# 12V_to_3V3.net
KiCad netlist of a schematic drawn in Altium Designer
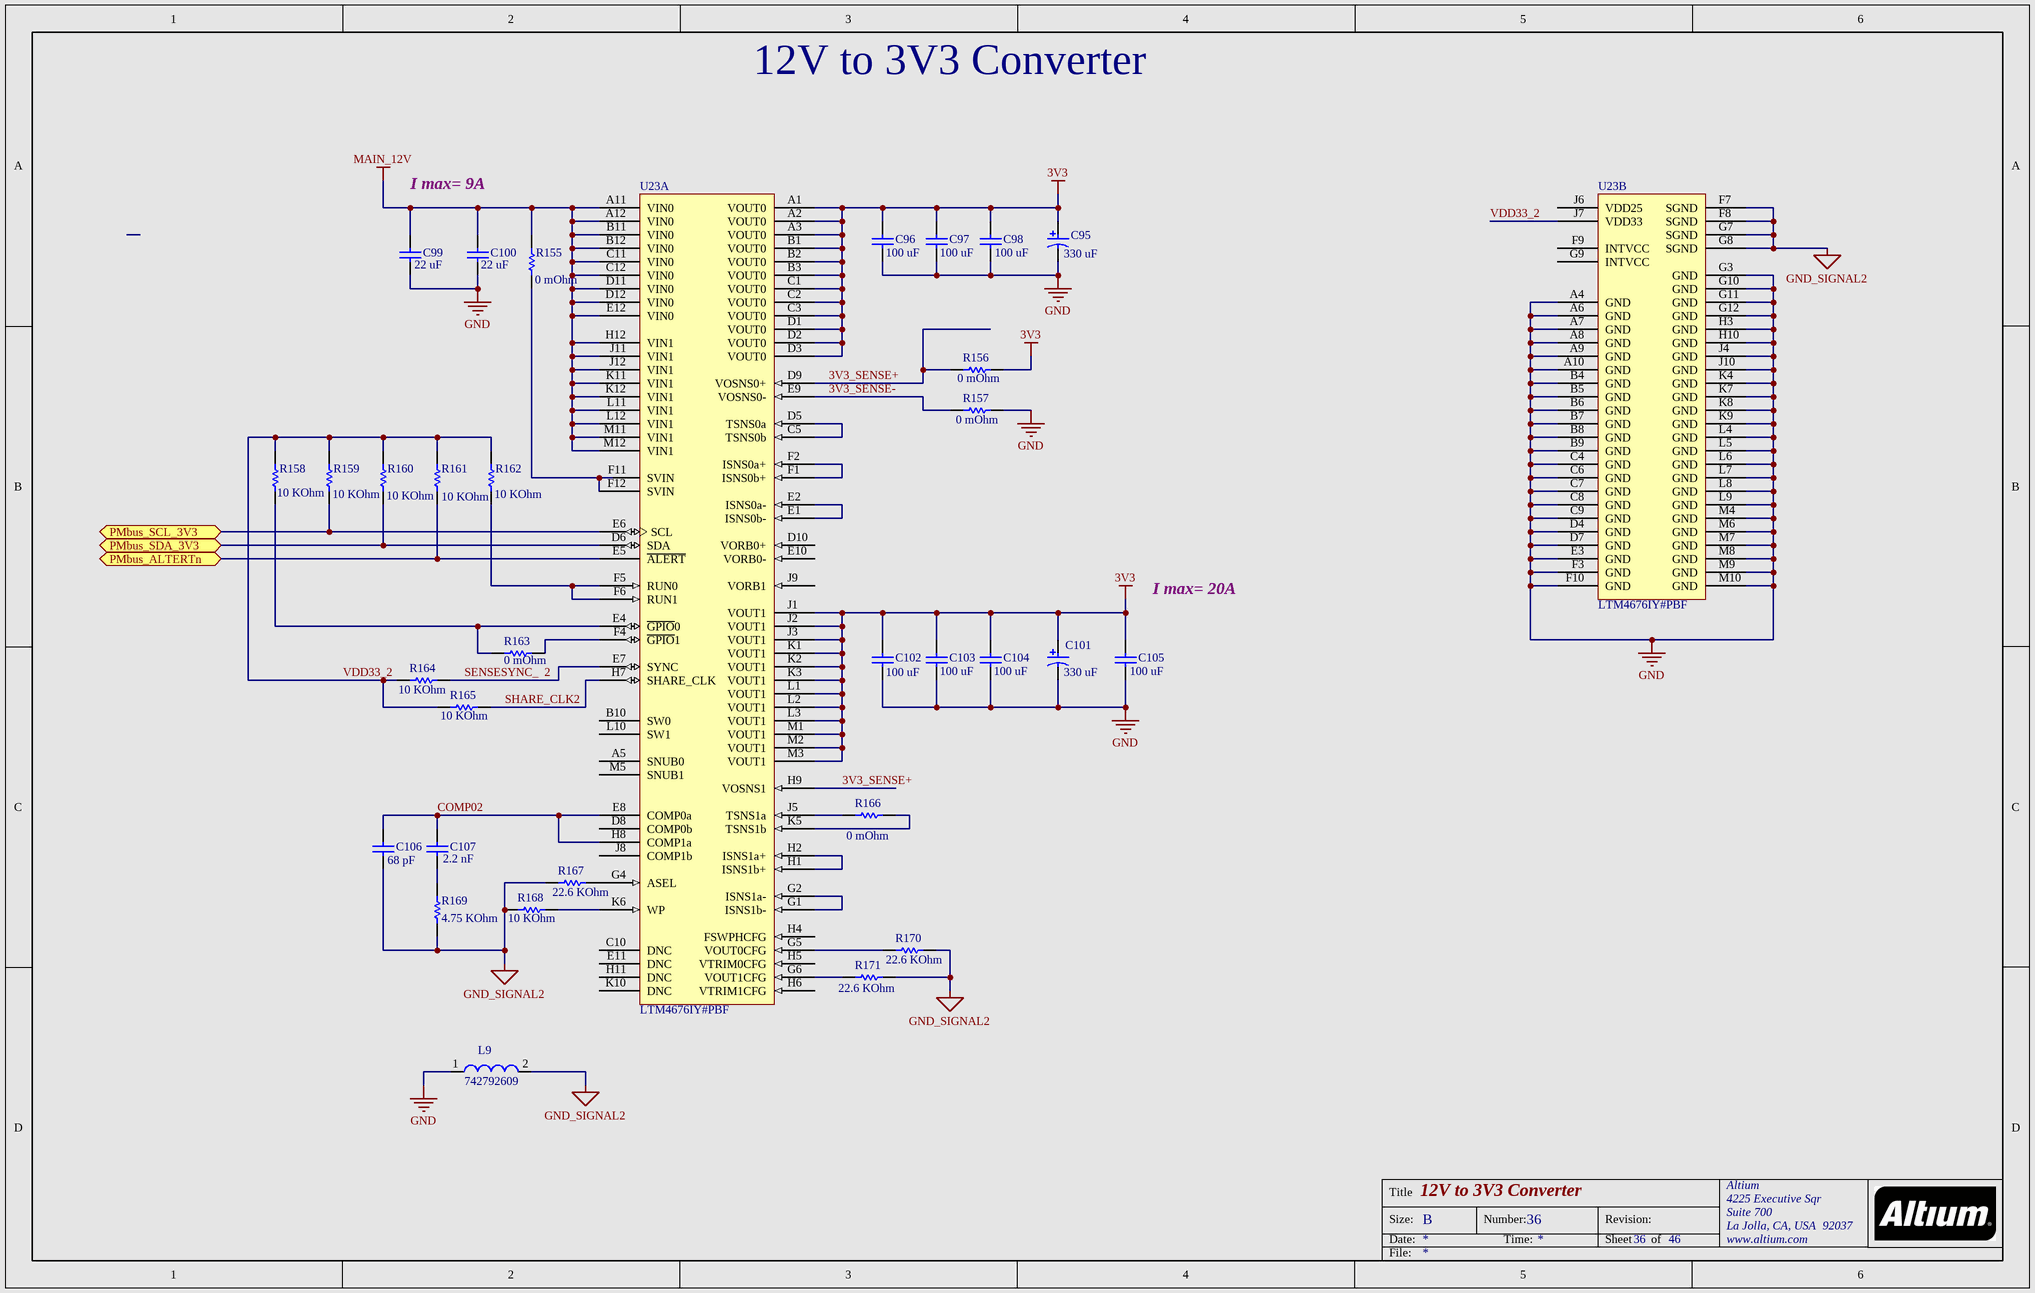
[diagram p0: 12V_to_3V3.SchDoc]

(export (version "E")
  (design (tool "Eeschema 10.0.6"))
  (components
    (comp (ref "C95")
      (value "6TPF330M9L")
      (footprint "PNSC-TPF-D3L_V")
      (description "Tantalum Capacitor, 330 uF, +/- 20%, 6.3 V, -55 to 105 degC, 2-Pin Molded, RoHS, Tape and Reel")
      (fields (field (name "CAPACITANCE") "330 uF"))
      (libsource (lib "Altium Content Vault") (part "CMP-1665-00019-2"))
    )
    (comp (ref "C96")
      (value "GRM31CR60J107ME39L")
      (footprint "CAPC3216X190X55ML30T25")
      (description "Chip Capacitor, 100 uF, +/- 20%, 6.3 V, -55 to 85 degC, 1206 (3216 Metric), RoHS, Tape and Reel")
      (fields (field (name "TOLERANCE") "20%") (field (name "CAPACITANCE") "100 uF"))
      (libsource (lib "Altium Content Vault") (part "CAP-NP-2"))
    )
    (comp (ref "C97")
      (value "GRM31CR60J107ME39L")
      (footprint "CAPC3216X190X55ML30T25")
      (description "Chip Capacitor, 100 uF, +/- 20%, 6.3 V, -55 to 85 degC, 1206 (3216 Metric), RoHS, Tape and Reel")
      (fields (field (name "TOLERANCE") "20%") (field (name "CAPACITANCE") "100 uF"))
      (libsource (lib "Altium Content Vault") (part "CAP-NP-2"))
    )
    (comp (ref "C98")
      (value "GRM31CR60J107ME39L")
      (footprint "CAPC3216X190X55ML30T25")
      (description "Chip Capacitor, 100 uF, +/- 20%, 6.3 V, -55 to 85 degC, 1206 (3216 Metric), RoHS, Tape and Reel")
      (fields (field (name "TOLERANCE") "20%") (field (name "CAPACITANCE") "100 uF"))
      (libsource (lib "Altium Content Vault") (part "CAP-NP-2"))
    )
    (comp (ref "C99")
      (value "GRM31CR61E226KE15L")
      (footprint "CAPC3216X180X55ML20T25")
      (description "Chip Capacitor, 22 uF, +/- 10%, 25 V, -55 to 85 degC, 1206 (3216 Metric), RoHS, Tape and Reel")
      (fields (field (name "TOLERANCE") "10%") (field (name "CAPACITANCE") "22 uF"))
      (libsource (lib "Altium Content Vault") (part "CAP-NP-2"))
    )
    (comp (ref "C100")
      (value "GRM31CR61E226KE15L")
      (footprint "CAPC3216X180X55ML20T25")
      (description "Chip Capacitor, 22 uF, +/- 10%, 25 V, -55 to 85 degC, 1206 (3216 Metric), RoHS, Tape and Reel")
      (fields (field (name "TOLERANCE") "10%") (field (name "CAPACITANCE") "22 uF"))
      (libsource (lib "Altium Content Vault") (part "CAP-NP-2"))
    )
    (comp (ref "C101")
      (value "6TPF330M9L")
      (footprint "PNSC-TPF-D3L_V")
      (description "Tantalum Capacitor, 330 uF, +/- 20%, 6.3 V, -55 to 105 degC, 2-Pin Molded, RoHS, Tape and Reel")
      (fields (field (name "CAPACITANCE") "330 uF"))
      (libsource (lib "Altium Content Vault") (part "CMP-1665-00019-2"))
    )
    (comp (ref "C102")
      (value "GRM31CR60J107ME39L")
      (footprint "CAPC3216X190X55ML30T25")
      (description "Chip Capacitor, 100 uF, +/- 20%, 6.3 V, -55 to 85 degC, 1206 (3216 Metric), RoHS, Tape and Reel")
      (fields (field (name "TOLERANCE") "20%") (field (name "CAPACITANCE") "100 uF"))
      (libsource (lib "Altium Content Vault") (part "CAP-NP-2"))
    )
    (comp (ref "C103")
      (value "GRM31CR60J107ME39L")
      (footprint "CAPC3216X190X55ML30T25")
      (description "Chip Capacitor, 100 uF, +/- 20%, 6.3 V, -55 to 85 degC, 1206 (3216 Metric), RoHS, Tape and Reel")
      (fields (field (name "TOLERANCE") "20%") (field (name "CAPACITANCE") "100 uF"))
      (libsource (lib "Altium Content Vault") (part "CAP-NP-2"))
    )
    (comp (ref "C104")
      (value "GRM31CR60J107ME39L")
      (footprint "CAPC3216X190X55ML30T25")
      (description "Chip Capacitor, 100 uF, +/- 20%, 6.3 V, -55 to 85 degC, 1206 (3216 Metric), RoHS, Tape and Reel")
      (fields (field (name "TOLERANCE") "20%") (field (name "CAPACITANCE") "100 uF"))
      (libsource (lib "Altium Content Vault") (part "CAP-NP-2"))
    )
    (comp (ref "C105")
      (value "GRM31CR60J107ME39L")
      (footprint "CAPC3216X190X55ML30T25")
      (description "Chip Capacitor, 100 uF, +/- 20%, 6.3 V, -55 to 85 degC, 1206 (3216 Metric), RoHS, Tape and Reel")
      (fields (field (name "TOLERANCE") "20%") (field (name "CAPACITANCE") "100 uF"))
      (libsource (lib "Altium Content Vault") (part "CAP-NP-2"))
    )
    (comp (ref "C106")
      (value "ECJ-0EC1H680J")
      (footprint "CAPC1005X55X20ML5T10")
      (description "Chip Capacitor, 68 pF, +/- 5%, 50 V, -55 to 125 degC, 0402 (1005 Metric), RoHS, Tape and Reel")
      (fields (field (name "TOLERANCE") "5%") (field (name "CAPACITANCE") "68 pF"))
      (libsource (lib "Altium Content Vault") (part "CMP-1665-00023-1"))
    )
    (comp (ref "C107")
      (value "CGJ2B2X7R1E222K050BA")
      (footprint "CAPC1005X55X10ML05")
      (description "Chip Capacitor, 2.2 nF, +/- 10%, 25 V, -55 to 125 degC, 0402 (1005 Metric), RoHS, Tape and Reel")
      (fields (field (name "TOLERANCE") "10%") (field (name "CAPACITANCE") "2.2 nF"))
      (libsource (lib "Altium Content Vault") (part "CAP-NP-2"))
    )
    (comp (ref "L9")
      (value "742792609")
      (footprint "SMD-0603")
      (description "SMD EMI Suppression Ferrite Bead WE-CBF, Z = 30 Ohm")
      (libsource (lib "Altium Content Vault") (part "CMP-0220-00193-1"))
    )
    (comp (ref "R155")
      (value "ERJ-2GE0R00X")
      (footprint "RESC1005X40X25ML05T05")
      (description "Chip Resistor, 0 mOhm, +/- 5%, 100 mW, -55 to 155 degC, 0402 (1005 Metric), RoHS, Tape and Reel")
      (fields
        (field (name "TOLERANCE") "5%")
        (field (name "RESISTANCE") "0 mOhm")
        (field (name "MANUFACTURER") "Basic Passives")
      )
      (libsource (lib "Altium Content Vault") (part "RES-2"))
    )
    (comp (ref "R156")
      (value "ERJ-2GE0R00X")
      (footprint "RESC1005X40X25ML05T05")
      (description "Chip Resistor, 0 mOhm, +/- 5%, 100 mW, -55 to 155 degC, 0402 (1005 Metric), RoHS, Tape and Reel")
      (fields
        (field (name "TOLERANCE") "5%")
        (field (name "RESISTANCE") "0 mOhm")
        (field (name "MANUFACTURER") "Basic Passives")
      )
      (libsource (lib "Altium Content Vault") (part "RES-2"))
    )
    (comp (ref "R157")
      (value "ERJ-2GE0R00X")
      (footprint "RESC1005X40X25ML05T05")
      (description "Chip Resistor, 0 mOhm, +/- 5%, 100 mW, -55 to 155 degC, 0402 (1005 Metric), RoHS, Tape and Reel")
      (fields
        (field (name "TOLERANCE") "5%")
        (field (name "RESISTANCE") "0 mOhm")
        (field (name "MANUFACTURER") "Basic Passives")
      )
      (libsource (lib "Altium Content Vault") (part "RES-2"))
    )
    (comp (ref "R158")
      (value "ERJ-2RKF1002X")
      (footprint "RESC1005X40X25NL05T05")
      (description "Chip Resistor, 10 KOhm, +/- 1%, 100 mW, -55 to 155 degC, 0402 (1005 Metric), RoHS, Tape and Reel")
      (fields
        (field (name "TOLERANCE") "1%")
        (field (name "RESISTANCE") "10 KOhm")
        (field (name "MANUFACTURER") "Basic Passives")
      )
      (libsource (lib "Altium Content Vault") (part "RES-2"))
    )
    (comp (ref "R159")
      (value "ERJ-2RKF1002X")
      (footprint "RESC1005X40X25NL05T05")
      (description "Chip Resistor, 10 KOhm, +/- 1%, 100 mW, -55 to 155 degC, 0402 (1005 Metric), RoHS, Tape and Reel")
      (fields
        (field (name "TOLERANCE") "1%")
        (field (name "RESISTANCE") "10 KOhm")
        (field (name "MANUFACTURER") "Basic Passives")
      )
      (libsource (lib "Altium Content Vault") (part "RES-2"))
    )
    (comp (ref "R160")
      (value "ERJ-2RKF1002X")
      (footprint "RESC1005X40X25NL05T05")
      (description "Chip Resistor, 10 KOhm, +/- 1%, 100 mW, -55 to 155 degC, 0402 (1005 Metric), RoHS, Tape and Reel")
      (fields
        (field (name "TOLERANCE") "1%")
        (field (name "RESISTANCE") "10 KOhm")
        (field (name "MANUFACTURER") "Basic Passives")
      )
      (libsource (lib "Altium Content Vault") (part "RES-2"))
    )
    (comp (ref "R161")
      (value "ERJ-2RKF1002X")
      (footprint "RESC1005X40X25NL05T05")
      (description "Chip Resistor, 10 KOhm, +/- 1%, 100 mW, -55 to 155 degC, 0402 (1005 Metric), RoHS, Tape and Reel")
      (fields
        (field (name "TOLERANCE") "1%")
        (field (name "RESISTANCE") "10 KOhm")
        (field (name "MANUFACTURER") "Basic Passives")
      )
      (libsource (lib "Altium Content Vault") (part "RES-2"))
    )
    (comp (ref "R162")
      (value "ERJ-2RKF1002X")
      (footprint "RESC1005X40X25NL05T05")
      (description "Chip Resistor, 10 KOhm, +/- 1%, 100 mW, -55 to 155 degC, 0402 (1005 Metric), RoHS, Tape and Reel")
      (fields
        (field (name "TOLERANCE") "1%")
        (field (name "RESISTANCE") "10 KOhm")
        (field (name "MANUFACTURER") "Basic Passives")
      )
      (libsource (lib "Altium Content Vault") (part "RES-2"))
    )
    (comp (ref "R163")
      (value "ERJ-2GE0R00X")
      (footprint "RESC1005X40X25ML05T05")
      (description "Chip Resistor, 0 mOhm, +/- 5%, 100 mW, -55 to 155 degC, 0402 (1005 Metric), RoHS, Tape and Reel")
      (fields
        (field (name "TOLERANCE") "5%")
        (field (name "RESISTANCE") "0 mOhm")
        (field (name "MANUFACTURER") "Basic Passives")
      )
      (libsource (lib "Altium Content Vault") (part "RES-2"))
    )
    (comp (ref "R164")
      (value "ERJ-2RKF1002X")
      (footprint "RESC1005X40X25NL05T05")
      (description "Chip Resistor, 10 KOhm, +/- 1%, 100 mW, -55 to 155 degC, 0402 (1005 Metric), RoHS, Tape and Reel")
      (fields
        (field (name "TOLERANCE") "1%")
        (field (name "RESISTANCE") "10 KOhm")
        (field (name "MANUFACTURER") "Basic Passives")
      )
      (libsource (lib "Altium Content Vault") (part "RES-2"))
    )
    (comp (ref "R165")
      (value "ERJ-2RKF1002X")
      (footprint "RESC1005X40X25NL05T05")
      (description "Chip Resistor, 10 KOhm, +/- 1%, 100 mW, -55 to 155 degC, 0402 (1005 Metric), RoHS, Tape and Reel")
      (fields
        (field (name "TOLERANCE") "1%")
        (field (name "RESISTANCE") "10 KOhm")
        (field (name "MANUFACTURER") "Basic Passives")
      )
      (libsource (lib "Altium Content Vault") (part "RES-2"))
    )
    (comp (ref "R166")
      (value "ERJ-2GE0R00X")
      (footprint "RESC1005X40X25ML05T05")
      (description "Chip Resistor, 0 mOhm, +/- 5%, 100 mW, -55 to 155 degC, 0402 (1005 Metric), RoHS, Tape and Reel")
      (fields
        (field (name "TOLERANCE") "5%")
        (field (name "RESISTANCE") "0 mOhm")
        (field (name "MANUFACTURER") "Basic Passives")
      )
      (libsource (lib "Altium Content Vault") (part "RES-2"))
    )
    (comp (ref "R167")
      (value "CRCW040222K6FKED")
      (footprint "RESC1005X40X25LL05T05")
      (description "Chip Resistor, 22.6 KOhm, +/- 1%, 63 mW, -55 to 155 degC, 0402 (1005 Metric), RoHS, Tape and Reel")
      (fields (field (name "RESISTANCE") "22.6 KOhm") (field (name "TOLERANCE") "1%"))
      (libsource (lib "Altium Content Vault") (part "RES"))
    )
    (comp (ref "R168")
      (value "ERJ-2RKF1002X")
      (footprint "RESC1005X40X25NL05T05")
      (description "Chip Resistor, 10 KOhm, +/- 1%, 100 mW, -55 to 155 degC, 0402 (1005 Metric), RoHS, Tape and Reel")
      (fields
        (field (name "TOLERANCE") "1%")
        (field (name "RESISTANCE") "10 KOhm")
        (field (name "MANUFACTURER") "Basic Passives")
      )
      (libsource (lib "Altium Content Vault") (part "RES-2"))
    )
    (comp (ref "R169")
      (value "ERJ-2RKF4751X")
      (footprint "RESC1005X40X25ML05T05")
      (description "Chip Resistor, 4.75 KOhm, +/- 1%, 100 mW, -55 to 155 degC, 0402 (1005 Metric), RoHS, Tape and Reel")
      (fields
        (field (name "RESISTANCE") "4.75 KOhm")
        (field (name "TOLERANCE") "1%")
        (field (name "MANUFACTURER") "Basic Passives")
      )
      (libsource (lib "Altium Content Vault") (part "RES-2"))
    )
    (comp (ref "R170")
      (value "CRCW040222K6FKED")
      (footprint "RESC1005X40X25LL05T05")
      (description "Chip Resistor, 22.6 KOhm, +/- 1%, 63 mW, -55 to 155 degC, 0402 (1005 Metric), RoHS, Tape and Reel")
      (fields (field (name "RESISTANCE") "22.6 KOhm") (field (name "TOLERANCE") "1%"))
      (libsource (lib "Altium Content Vault") (part "RES"))
    )
    (comp (ref "R171")
      (value "CRCW040222K6FKED")
      (footprint "RESC1005X40X25LL05T05")
      (description "Chip Resistor, 22.6 KOhm, +/- 1%, 63 mW, -55 to 155 degC, 0402 (1005 Metric), RoHS, Tape and Reel")
      (fields (field (name "RESISTANCE") "22.6 KOhm") (field (name "TOLERANCE") "1%"))
      (libsource (lib "Altium Content Vault") (part "RES"))
    )
    (comp (ref "U23")
      (value "LTM4676IY#PBF")
      (footprint "LT-BGA-144-05-08-1920_V")
      (libsource (lib "Altium Content Vault") (part "LT-LTM4676-BGA-144"))
    )
  )
  (nets
    (net (code "1") (name "/3V3_SENSE+") (class "Default")
      (node (ref "R156") (pin "1") (pinfunction "1_1") (pintype "passive"))
      (node (ref "U23") (pin "D9") (pinfunction "VOSNS0+_D9") (pintype "input"))
      (node (ref "U23") (pin "H9") (pinfunction "VOSNS1_H9") (pintype "input"))
    )
    (net (code "2") (name "/3V3_SENSE-") (class "Default")
      (node (ref "R157") (pin "1") (pinfunction "1_1") (pintype "passive"))
      (node (ref "U23") (pin "E9") (pinfunction "VOSNS0-_E9") (pintype "input"))
    )
    (net (code "3") (name "/COMP02") (class "Default")
      (node (ref "C106") (pin "2") (pinfunction "2_2") (pintype "passive"))
      (node (ref "C107") (pin "2") (pinfunction "2_2") (pintype "passive"))
      (node (ref "U23") (pin "E8") (pinfunction "COMP0a_E8") (pintype "passive"))
      (node (ref "U23") (pin "H8") (pinfunction "COMP1a_H8") (pintype "passive"))
    )
    (net (code "4") (name "/PMbus_ALTERTn") (class "Default")
      (node (ref "R161") (pin "1") (pinfunction "1_1") (pintype "passive"))
      (node (ref "U23") (pin "E5") (pinfunction "~{ALERT}_E5") (pintype "open_collector"))
    )
    (net (code "5") (name "/PMbus_SCL_3V3") (class "Default")
      (node (ref "R159") (pin "1") (pinfunction "1_1") (pintype "passive"))
      (node (ref "U23") (pin "E6") (pinfunction "SCL_E6") (pintype "bidirectional"))
    )
    (net (code "6") (name "/PMbus_SDA_3V3") (class "Default")
      (node (ref "R160") (pin "1") (pinfunction "1_1") (pintype "passive"))
      (node (ref "U23") (pin "D6") (pinfunction "SDA_D6") (pintype "bidirectional"))
    )
    (net (code "7") (name "/SENSESYNC_  2") (class "Default")
      (node (ref "R164") (pin "1") (pinfunction "1_1") (pintype "passive"))
      (node (ref "U23") (pin "E7") (pinfunction "SYNC_E7") (pintype "bidirectional"))
    )
    (net (code "8") (name "/SHARE_CLK2") (class "Default")
      (node (ref "R165") (pin "1") (pinfunction "1_1") (pintype "passive"))
      (node (ref "U23") (pin "H7") (pinfunction "SHARE_CLK_H7") (pintype "bidirectional"))
    )
    (net (code "9") (name "/VDD33_2") (class "Default")
      (node (ref "R158") (pin "2") (pinfunction "2_2") (pintype "passive"))
      (node (ref "R159") (pin "2") (pinfunction "2_2") (pintype "passive"))
      (node (ref "R160") (pin "2") (pinfunction "2_2") (pintype "passive"))
      (node (ref "R161") (pin "2") (pinfunction "2_2") (pintype "passive"))
      (node (ref "R162") (pin "2") (pinfunction "2_2") (pintype "passive"))
      (node (ref "R164") (pin "2") (pinfunction "2_2") (pintype "passive"))
      (node (ref "R165") (pin "2") (pinfunction "2_2") (pintype "passive"))
      (node (ref "U23") (pin "J7") (pinfunction "VDD33_J7") (pintype "power_in"))
    )
    (net (code "10") (name "3V3") (class "Default")
      (node (ref "C101") (pin "1") (pinfunction "1_1") (pintype "passive"))
      (node (ref "C102") (pin "2") (pinfunction "2_2") (pintype "passive"))
      (node (ref "C103") (pin "2") (pinfunction "2_2") (pintype "passive"))
      (node (ref "C104") (pin "2") (pinfunction "2_2") (pintype "passive"))
      (node (ref "C105") (pin "2") (pinfunction "2_2") (pintype "passive"))
      (node (ref "C95") (pin "1") (pinfunction "1_1") (pintype "passive"))
      (node (ref "C96") (pin "2") (pinfunction "2_2") (pintype "passive"))
      (node (ref "C97") (pin "2") (pinfunction "2_2") (pintype "passive"))
      (node (ref "C98") (pin "2") (pinfunction "2_2") (pintype "passive"))
      (node (ref "R156") (pin "2") (pinfunction "2_2") (pintype "passive"))
      (node (ref "U23") (pin "A1") (pinfunction "VOUT0_A1") (pintype "power_in"))
      (node (ref "U23") (pin "A2") (pinfunction "VOUT0_A2") (pintype "power_in"))
      (node (ref "U23") (pin "A3") (pinfunction "VOUT0_A3") (pintype "power_in"))
      (node (ref "U23") (pin "B1") (pinfunction "VOUT0_B1") (pintype "power_in"))
      (node (ref "U23") (pin "B2") (pinfunction "VOUT0_B2") (pintype "power_in"))
      (node (ref "U23") (pin "B3") (pinfunction "VOUT0_B3") (pintype "power_in"))
      (node (ref "U23") (pin "C1") (pinfunction "VOUT0_C1") (pintype "power_in"))
      (node (ref "U23") (pin "C2") (pinfunction "VOUT0_C2") (pintype "power_in"))
      (node (ref "U23") (pin "C3") (pinfunction "VOUT0_C3") (pintype "power_in"))
      (node (ref "U23") (pin "D1") (pinfunction "VOUT0_D1") (pintype "power_in"))
      (node (ref "U23") (pin "D2") (pinfunction "VOUT0_D2") (pintype "power_in"))
      (node (ref "U23") (pin "D3") (pinfunction "VOUT0_D3") (pintype "power_in"))
      (node (ref "U23") (pin "J1") (pinfunction "VOUT1_J1") (pintype "power_in"))
      (node (ref "U23") (pin "J2") (pinfunction "VOUT1_J2") (pintype "power_in"))
      (node (ref "U23") (pin "J3") (pinfunction "VOUT1_J3") (pintype "power_in"))
      (node (ref "U23") (pin "K1") (pinfunction "VOUT1_K1") (pintype "power_in"))
      (node (ref "U23") (pin "K2") (pinfunction "VOUT1_K2") (pintype "power_in"))
      (node (ref "U23") (pin "K3") (pinfunction "VOUT1_K3") (pintype "power_in"))
      (node (ref "U23") (pin "L1") (pinfunction "VOUT1_L1") (pintype "power_in"))
      (node (ref "U23") (pin "L2") (pinfunction "VOUT1_L2") (pintype "power_in"))
      (node (ref "U23") (pin "L3") (pinfunction "VOUT1_L3") (pintype "power_in"))
      (node (ref "U23") (pin "M1") (pinfunction "VOUT1_M1") (pintype "power_in"))
      (node (ref "U23") (pin "M2") (pinfunction "VOUT1_M2") (pintype "power_in"))
      (node (ref "U23") (pin "M3") (pinfunction "VOUT1_M3") (pintype "power_in"))
    )
    (net (code "11") (name "GND") (class "Default")
      (node (ref "C100") (pin "1") (pinfunction "1_1") (pintype "passive"))
      (node (ref "C101") (pin "2") (pinfunction "2_2") (pintype "passive"))
      (node (ref "C102") (pin "1") (pinfunction "1_1") (pintype "passive"))
      (node (ref "C103") (pin "1") (pinfunction "1_1") (pintype "passive"))
      (node (ref "C104") (pin "1") (pinfunction "1_1") (pintype "passive"))
      (node (ref "C105") (pin "1") (pinfunction "1_1") (pintype "passive"))
      (node (ref "C95") (pin "2") (pinfunction "2_2") (pintype "passive"))
      (node (ref "C96") (pin "1") (pinfunction "1_1") (pintype "passive"))
      (node (ref "C97") (pin "1") (pinfunction "1_1") (pintype "passive"))
      (node (ref "C98") (pin "1") (pinfunction "1_1") (pintype "passive"))
      (node (ref "C99") (pin "1") (pinfunction "1_1") (pintype "passive"))
      (node (ref "L9") (pin "1") (pinfunction "1_1") (pintype "passive"))
      (node (ref "R157") (pin "2") (pinfunction "2_2") (pintype "passive"))
      (node (ref "U23") (pin "A10") (pinfunction "GND_A10") (pintype "power_in"))
      (node (ref "U23") (pin "A4") (pinfunction "GND_A4") (pintype "power_in"))
      (node (ref "U23") (pin "A6") (pinfunction "GND_A6") (pintype "power_in"))
      (node (ref "U23") (pin "A7") (pinfunction "GND_A7") (pintype "power_in"))
      (node (ref "U23") (pin "A8") (pinfunction "GND_A8") (pintype "power_in"))
      (node (ref "U23") (pin "A9") (pinfunction "GND_A9") (pintype "power_in"))
      (node (ref "U23") (pin "B4") (pinfunction "GND_B4") (pintype "power_in"))
      (node (ref "U23") (pin "B5") (pinfunction "GND_B5") (pintype "power_in"))
      (node (ref "U23") (pin "B6") (pinfunction "GND_B6") (pintype "power_in"))
      (node (ref "U23") (pin "B7") (pinfunction "GND_B7") (pintype "power_in"))
      (node (ref "U23") (pin "B8") (pinfunction "GND_B8") (pintype "power_in"))
      (node (ref "U23") (pin "B9") (pinfunction "GND_B9") (pintype "power_in"))
      (node (ref "U23") (pin "C4") (pinfunction "GND_C4") (pintype "power_in"))
      (node (ref "U23") (pin "C6") (pinfunction "GND_C6") (pintype "power_in"))
      (node (ref "U23") (pin "C7") (pinfunction "GND_C7") (pintype "power_in"))
      (node (ref "U23") (pin "C8") (pinfunction "GND_C8") (pintype "power_in"))
      (node (ref "U23") (pin "C9") (pinfunction "GND_C9") (pintype "power_in"))
      (node (ref "U23") (pin "D4") (pinfunction "GND_D4") (pintype "power_in"))
      (node (ref "U23") (pin "D7") (pinfunction "GND_D7") (pintype "power_in"))
      (node (ref "U23") (pin "E3") (pinfunction "GND_E3") (pintype "power_in"))
      (node (ref "U23") (pin "F10") (pinfunction "GND_F10") (pintype "power_in"))
      (node (ref "U23") (pin "F3") (pinfunction "GND_F3") (pintype "power_in"))
      (node (ref "U23") (pin "G10") (pinfunction "GND_G10") (pintype "power_in"))
      (node (ref "U23") (pin "G11") (pinfunction "GND_G11") (pintype "power_in"))
      (node (ref "U23") (pin "G12") (pinfunction "GND_G12") (pintype "power_in"))
      (node (ref "U23") (pin "G3") (pinfunction "GND_G3") (pintype "power_in"))
      (node (ref "U23") (pin "H10") (pinfunction "GND_H10") (pintype "power_in"))
      (node (ref "U23") (pin "H3") (pinfunction "GND_H3") (pintype "power_in"))
      (node (ref "U23") (pin "J10") (pinfunction "GND_J10") (pintype "power_in"))
      (node (ref "U23") (pin "J4") (pinfunction "GND_J4") (pintype "power_in"))
      (node (ref "U23") (pin "K4") (pinfunction "GND_K4") (pintype "power_in"))
      (node (ref "U23") (pin "K7") (pinfunction "GND_K7") (pintype "power_in"))
      (node (ref "U23") (pin "K8") (pinfunction "GND_K8") (pintype "power_in"))
      (node (ref "U23") (pin "K9") (pinfunction "GND_K9") (pintype "power_in"))
      (node (ref "U23") (pin "L4") (pinfunction "GND_L4") (pintype "power_in"))
      (node (ref "U23") (pin "L5") (pinfunction "GND_L5") (pintype "power_in"))
      (node (ref "U23") (pin "L6") (pinfunction "GND_L6") (pintype "power_in"))
      (node (ref "U23") (pin "L7") (pinfunction "GND_L7") (pintype "power_in"))
      (node (ref "U23") (pin "L8") (pinfunction "GND_L8") (pintype "power_in"))
      (node (ref "U23") (pin "L9") (pinfunction "GND_L9") (pintype "power_in"))
      (node (ref "U23") (pin "M10") (pinfunction "GND_M10") (pintype "power_in"))
      (node (ref "U23") (pin "M4") (pinfunction "GND_M4") (pintype "power_in"))
      (node (ref "U23") (pin "M6") (pinfunction "GND_M6") (pintype "power_in"))
      (node (ref "U23") (pin "M7") (pinfunction "GND_M7") (pintype "power_in"))
      (node (ref "U23") (pin "M8") (pinfunction "GND_M8") (pintype "power_in"))
      (node (ref "U23") (pin "M9") (pinfunction "GND_M9") (pintype "power_in"))
    )
    (net (code "12") (name "GND_SIGNAL2") (class "Default")
      (node (ref "C106") (pin "1") (pinfunction "1_1") (pintype "passive"))
      (node (ref "L9") (pin "2") (pinfunction "2_2") (pintype "passive"))
      (node (ref "R167") (pin "1") (pinfunction "1_1") (pintype "passive"))
      (node (ref "R168") (pin "2") (pinfunction "2_2") (pintype "passive"))
      (node (ref "R169") (pin "1") (pinfunction "1_1") (pintype "passive"))
      (node (ref "R170") (pin "2") (pinfunction "2_2") (pintype "passive"))
      (node (ref "R171") (pin "2") (pinfunction "2_2") (pintype "passive"))
      (node (ref "U23") (pin "F7") (pinfunction "SGND_F7") (pintype "power_in"))
      (node (ref "U23") (pin "F8") (pinfunction "SGND_F8") (pintype "power_in"))
      (node (ref "U23") (pin "G7") (pinfunction "SGND_G7") (pintype "power_in"))
      (node (ref "U23") (pin "G8") (pinfunction "SGND_G8") (pintype "power_in"))
    )
    (net (code "13") (name "MAIN_12V") (class "Default")
      (node (ref "C100") (pin "2") (pinfunction "2_2") (pintype "passive"))
      (node (ref "C99") (pin "2") (pinfunction "2_2") (pintype "passive"))
      (node (ref "R155") (pin "2") (pinfunction "2_2") (pintype "passive"))
      (node (ref "U23") (pin "A11") (pinfunction "VIN0_A11") (pintype "power_in"))
      (node (ref "U23") (pin "A12") (pinfunction "VIN0_A12") (pintype "power_in"))
      (node (ref "U23") (pin "B11") (pinfunction "VIN0_B11") (pintype "power_in"))
      (node (ref "U23") (pin "B12") (pinfunction "VIN0_B12") (pintype "power_in"))
      (node (ref "U23") (pin "C11") (pinfunction "VIN0_C11") (pintype "power_in"))
      (node (ref "U23") (pin "C12") (pinfunction "VIN0_C12") (pintype "power_in"))
      (node (ref "U23") (pin "D11") (pinfunction "VIN0_D11") (pintype "power_in"))
      (node (ref "U23") (pin "D12") (pinfunction "VIN0_D12") (pintype "power_in"))
      (node (ref "U23") (pin "E12") (pinfunction "VIN0_E12") (pintype "power_in"))
      (node (ref "U23") (pin "H12") (pinfunction "VIN1_H12") (pintype "power_in"))
      (node (ref "U23") (pin "J11") (pinfunction "VIN1_J11") (pintype "power_in"))
      (node (ref "U23") (pin "J12") (pinfunction "VIN1_J12") (pintype "power_in"))
      (node (ref "U23") (pin "K11") (pinfunction "VIN1_K11") (pintype "power_in"))
      (node (ref "U23") (pin "K12") (pinfunction "VIN1_K12") (pintype "power_in"))
      (node (ref "U23") (pin "L11") (pinfunction "VIN1_L11") (pintype "power_in"))
      (node (ref "U23") (pin "L12") (pinfunction "VIN1_L12") (pintype "power_in"))
      (node (ref "U23") (pin "M11") (pinfunction "VIN1_M11") (pintype "power_in"))
      (node (ref "U23") (pin "M12") (pinfunction "VIN1_M12") (pintype "power_in"))
    )
    (net (code "14") (name "Net-(C107-Pad1)") (class "Default")
      (node (ref "C107") (pin "1") (pinfunction "1_1") (pintype "passive"))
      (node (ref "R169") (pin "2") (pinfunction "2_2") (pintype "passive"))
    )
    (net (code "15") (name "Net-(R155-Pad1)") (class "Default")
      (node (ref "R155") (pin "1") (pinfunction "1_1") (pintype "passive"))
      (node (ref "U23") (pin "F11") (pinfunction "SVIN_F11") (pintype "power_in"))
      (node (ref "U23") (pin "F12") (pinfunction "SVIN_F12") (pintype "power_in"))
    )
    (net (code "16") (name "Net-(U23A-ASEL)") (class "Default")
      (node (ref "R167") (pin "2") (pinfunction "2_2") (pintype "passive"))
      (node (ref "U23") (pin "G4") (pinfunction "ASEL_G4") (pintype "input"))
    )
    (net (code "17") (name "Net-(U23A-ISNS0a+)") (class "Default")
      (node (ref "U23") (pin "F1") (pinfunction "ISNS0b+_F1") (pintype "input"))
      (node (ref "U23") (pin "F2") (pinfunction "ISNS0a+_F2") (pintype "input"))
    )
    (net (code "18") (name "Net-(U23A-ISNS0a-)") (class "Default")
      (node (ref "U23") (pin "E1") (pinfunction "ISNS0b-_E1") (pintype "input"))
      (node (ref "U23") (pin "E2") (pinfunction "ISNS0a-_E2") (pintype "input"))
    )
    (net (code "19") (name "Net-(U23A-ISNS1a+)") (class "Default")
      (node (ref "U23") (pin "H1") (pinfunction "ISNS1b+_H1") (pintype "input"))
      (node (ref "U23") (pin "H2") (pinfunction "ISNS1a+_H2") (pintype "input"))
    )
    (net (code "20") (name "Net-(U23A-ISNS1a-)") (class "Default")
      (node (ref "U23") (pin "G1") (pinfunction "ISNS1b-_G1") (pintype "input"))
      (node (ref "U23") (pin "G2") (pinfunction "ISNS1a-_G2") (pintype "input"))
    )
    (net (code "21") (name "Net-(U23A-RUN0)") (class "Default")
      (node (ref "R162") (pin "1") (pinfunction "1_1") (pintype "passive"))
      (node (ref "U23") (pin "F5") (pinfunction "RUN0_F5") (pintype "input"))
      (node (ref "U23") (pin "F6") (pinfunction "RUN1_F6") (pintype "input"))
    )
    (net (code "22") (name "Net-(U23A-TSNS0a)") (class "Default")
      (node (ref "U23") (pin "C5") (pinfunction "TSNS0b_C5") (pintype "input"))
      (node (ref "U23") (pin "D5") (pinfunction "TSNS0a_D5") (pintype "input"))
    )
    (net (code "23") (name "Net-(U23A-TSNS1a)") (class "Default")
      (node (ref "R166") (pin "1") (pinfunction "1_1") (pintype "passive"))
      (node (ref "U23") (pin "J5") (pinfunction "TSNS1a_J5") (pintype "input"))
    )
    (net (code "24") (name "Net-(U23A-TSNS1b)") (class "Default")
      (node (ref "R166") (pin "2") (pinfunction "2_2") (pintype "passive"))
      (node (ref "U23") (pin "K5") (pinfunction "TSNS1b_K5") (pintype "input"))
    )
    (net (code "25") (name "Net-(U23A-VOUT0CFG)") (class "Default")
      (node (ref "R170") (pin "1") (pinfunction "1_1") (pintype "passive"))
      (node (ref "U23") (pin "G5") (pinfunction "VOUT0CFG_G5") (pintype "input"))
    )
    (net (code "26") (name "Net-(U23A-VOUT1CFG)") (class "Default")
      (node (ref "R171") (pin "1") (pinfunction "1_1") (pintype "passive"))
      (node (ref "U23") (pin "G6") (pinfunction "VOUT1CFG_G6") (pintype "input"))
    )
    (net (code "27") (name "Net-(U23A-WP)") (class "Default")
      (node (ref "R168") (pin "1") (pinfunction "1_1") (pintype "passive"))
      (node (ref "U23") (pin "K6") (pinfunction "WP_K6") (pintype "input"))
    )
    (net (code "28") (name "Net-(U23A-~{GPIO}0)") (class "Default")
      (node (ref "R158") (pin "1") (pinfunction "1_1") (pintype "passive"))
      (node (ref "R163") (pin "2") (pinfunction "2_2") (pintype "passive"))
      (node (ref "U23") (pin "E4") (pinfunction "~{GPIO}0_E4") (pintype "bidirectional"))
    )
    (net (code "29") (name "Net-(U23A-~{GPIO}1)") (class "Default")
      (node (ref "R163") (pin "1") (pinfunction "1_1") (pintype "passive"))
      (node (ref "U23") (pin "F4") (pinfunction "~{GPIO}1_F4") (pintype "bidirectional"))
    )
    (net (code "30") (name "unconnected-(U23A-COMP0b-PadD8)") (class "Default")
      (node (ref "U23") (pin "D8") (pinfunction "COMP0b_D8") (pintype "passive"))
    )
    (net (code "31") (name "unconnected-(U23A-COMP1b-PadJ8)") (class "Default")
      (node (ref "U23") (pin "J8") (pinfunction "COMP1b_J8") (pintype "passive"))
    )
    (net (code "32") (name "unconnected-(U23A-DNC-PadC10)") (class "Default")
      (node (ref "U23") (pin "C10") (pinfunction "DNC_C10") (pintype "passive"))
    )
    (net (code "33") (name "unconnected-(U23A-DNC-PadE11)") (class "Default")
      (node (ref "U23") (pin "E11") (pinfunction "DNC_E11") (pintype "passive"))
    )
    (net (code "34") (name "unconnected-(U23A-DNC-PadH11)") (class "Default")
      (node (ref "U23") (pin "H11") (pinfunction "DNC_H11") (pintype "passive"))
    )
    (net (code "35") (name "unconnected-(U23A-DNC-PadK10)") (class "Default")
      (node (ref "U23") (pin "K10") (pinfunction "DNC_K10") (pintype "passive"))
    )
    (net (code "36") (name "unconnected-(U23A-FSWPHCFG-PadH4)") (class "Default")
      (node (ref "U23") (pin "H4") (pinfunction "FSWPHCFG_H4") (pintype "input"))
    )
    (net (code "37") (name "unconnected-(U23A-SNUB0-PadA5)") (class "Default")
      (node (ref "U23") (pin "A5") (pinfunction "SNUB0_A5") (pintype "passive"))
    )
    (net (code "38") (name "unconnected-(U23A-SNUB1-PadM5)") (class "Default")
      (node (ref "U23") (pin "M5") (pinfunction "SNUB1_M5") (pintype "passive"))
    )
    (net (code "39") (name "unconnected-(U23A-SW0-PadB10)") (class "Default")
      (node (ref "U23") (pin "B10") (pinfunction "SW0_B10") (pintype "passive"))
    )
    (net (code "40") (name "unconnected-(U23A-SW1-PadL10)") (class "Default")
      (node (ref "U23") (pin "L10") (pinfunction "SW1_L10") (pintype "passive"))
    )
    (net (code "41") (name "unconnected-(U23A-VORB0+-PadD10)") (class "Default")
      (node (ref "U23") (pin "D10") (pinfunction "VORB0+_D10") (pintype "input"))
    )
    (net (code "42") (name "unconnected-(U23A-VORB0--PadE10)") (class "Default")
      (node (ref "U23") (pin "E10") (pinfunction "VORB0-_E10") (pintype "input"))
    )
    (net (code "43") (name "unconnected-(U23A-VORB1-PadJ9)") (class "Default")
      (node (ref "U23") (pin "J9") (pinfunction "VORB1_J9") (pintype "input"))
    )
    (net (code "44") (name "unconnected-(U23A-VTRIM0CFG-PadH5)") (class "Default")
      (node (ref "U23") (pin "H5") (pinfunction "VTRIM0CFG_H5") (pintype "input"))
    )
    (net (code "45") (name "unconnected-(U23A-VTRIM1CFG-PadH6)") (class "Default")
      (node (ref "U23") (pin "H6") (pinfunction "VTRIM1CFG_H6") (pintype "input"))
    )
    (net (code "46") (name "unconnected-(U23B-INTVCC-PadF9)") (class "Default")
      (node (ref "U23") (pin "F9") (pinfunction "INTVCC_F9") (pintype "power_in"))
    )
    (net (code "47") (name "unconnected-(U23B-INTVCC-PadG9)") (class "Default")
      (node (ref "U23") (pin "G9") (pinfunction "INTVCC_G9") (pintype "power_in"))
    )
    (net (code "48") (name "unconnected-(U23B-VDD25-PadJ6)") (class "Default")
      (node (ref "U23") (pin "J6") (pinfunction "VDD25_J6") (pintype "power_in"))
    )
  )
)
